# stromplatine3.net
KiCad netlist of a schematic drawn in EAGLE
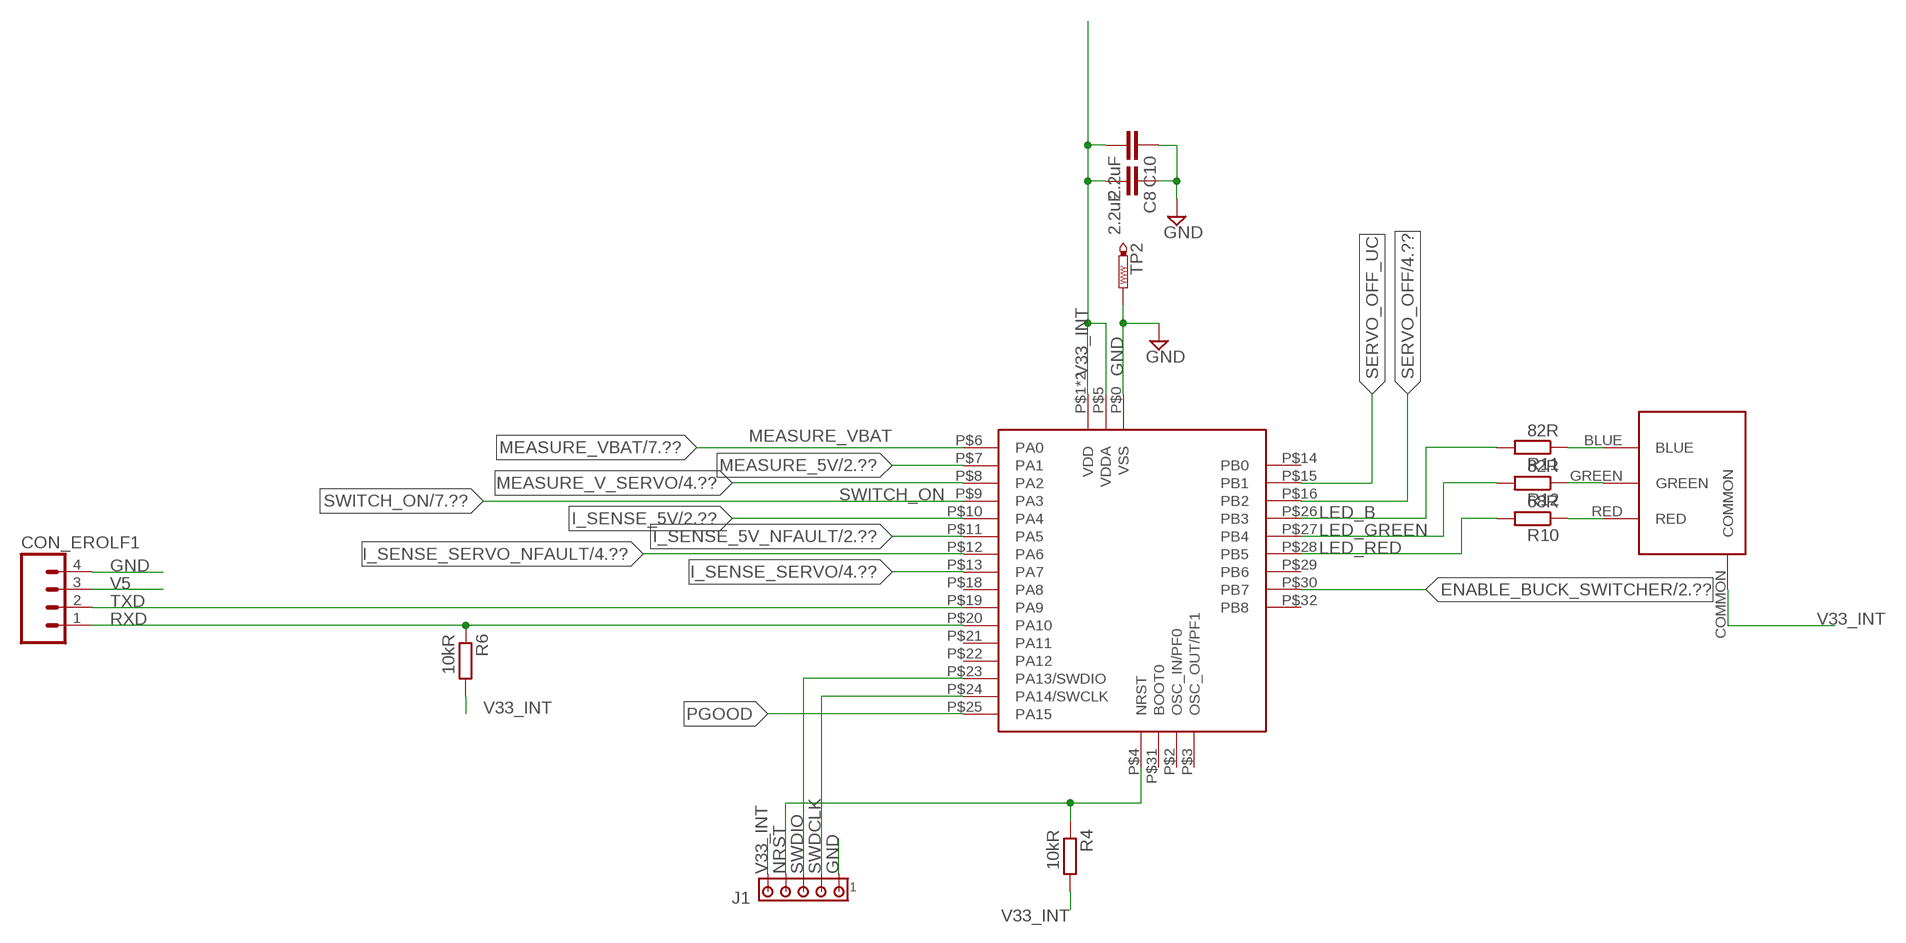
[diagram p0: schematic, sheet 1]
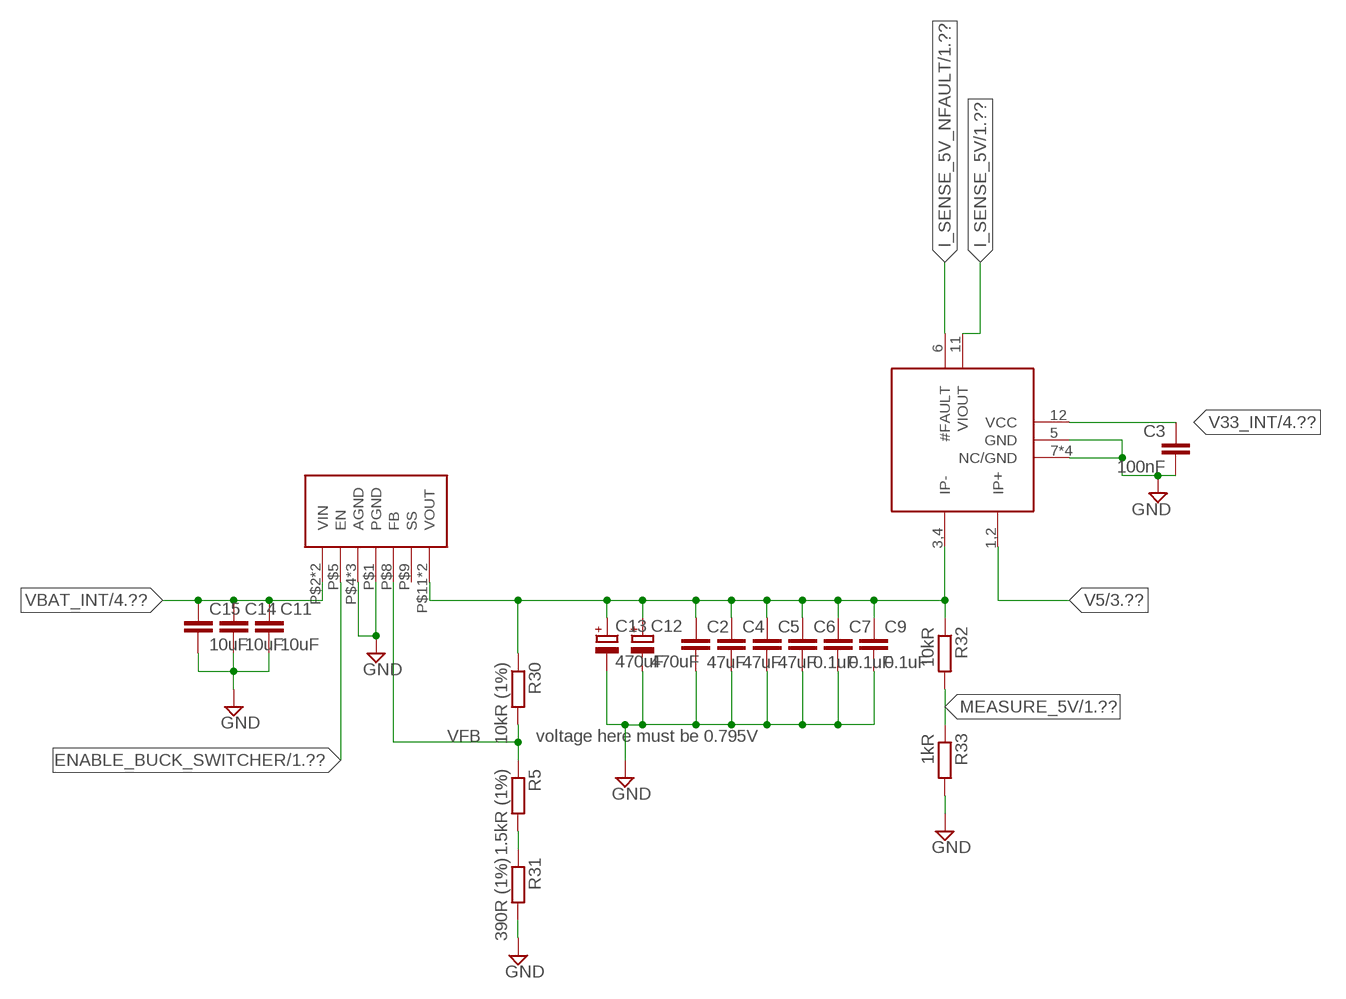
[diagram p1: schematic, sheet 2]
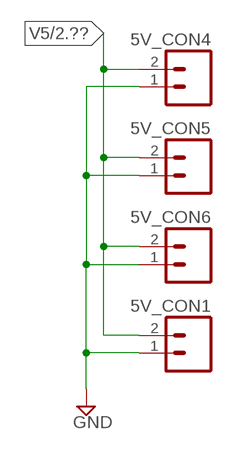
[diagram p2: schematic, sheet 3]
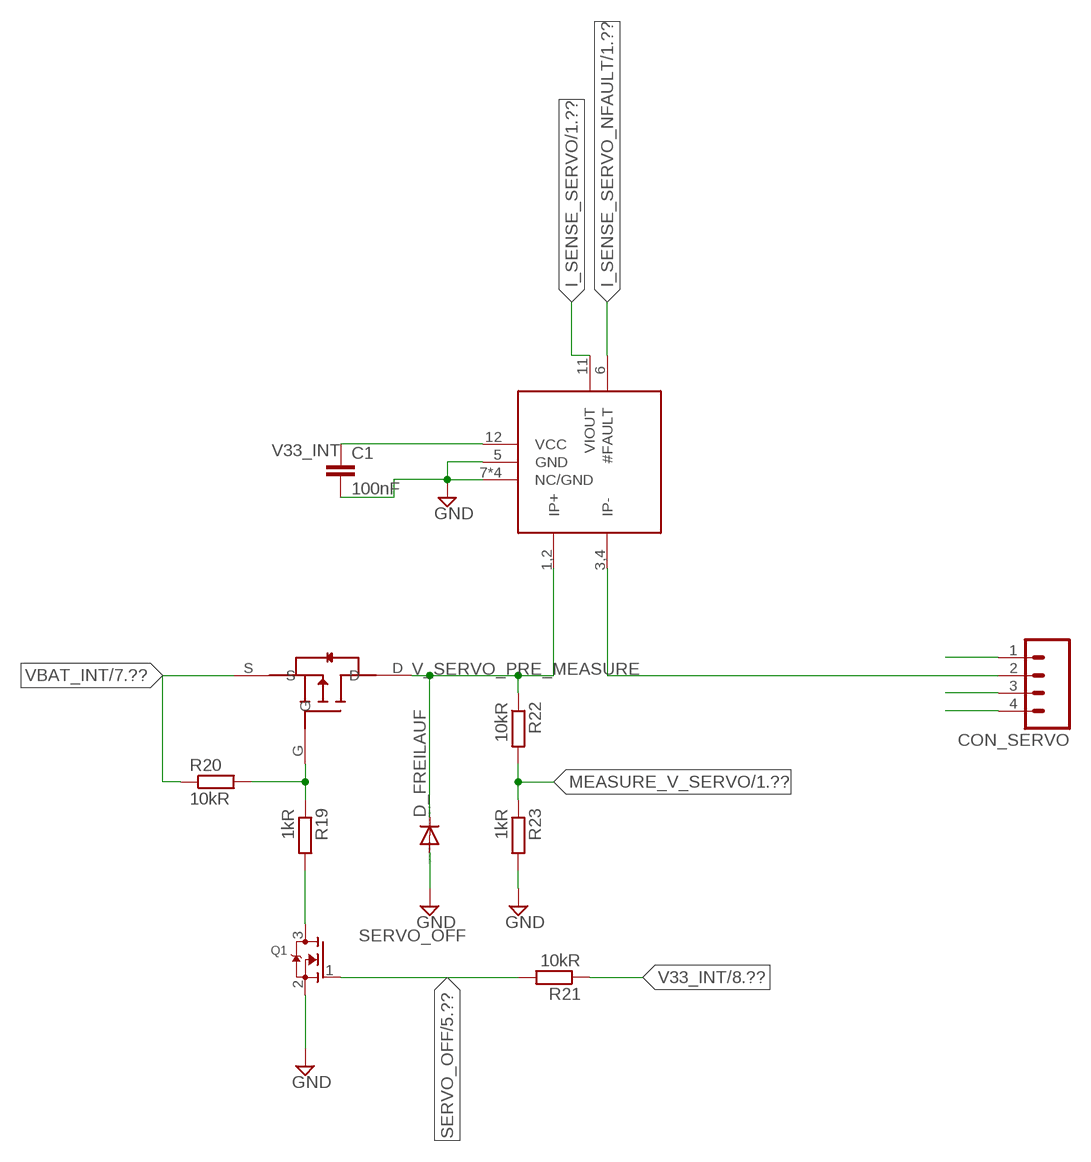
[diagram p3: schematic, sheet 4]
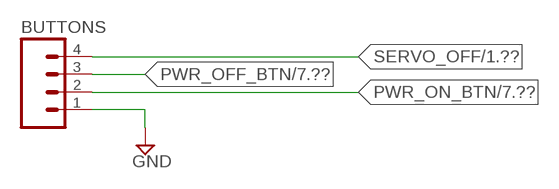
[diagram p4: schematic, sheet 5]
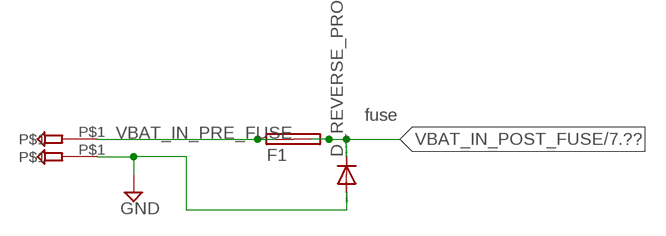
[diagram p5: schematic, sheet 6]
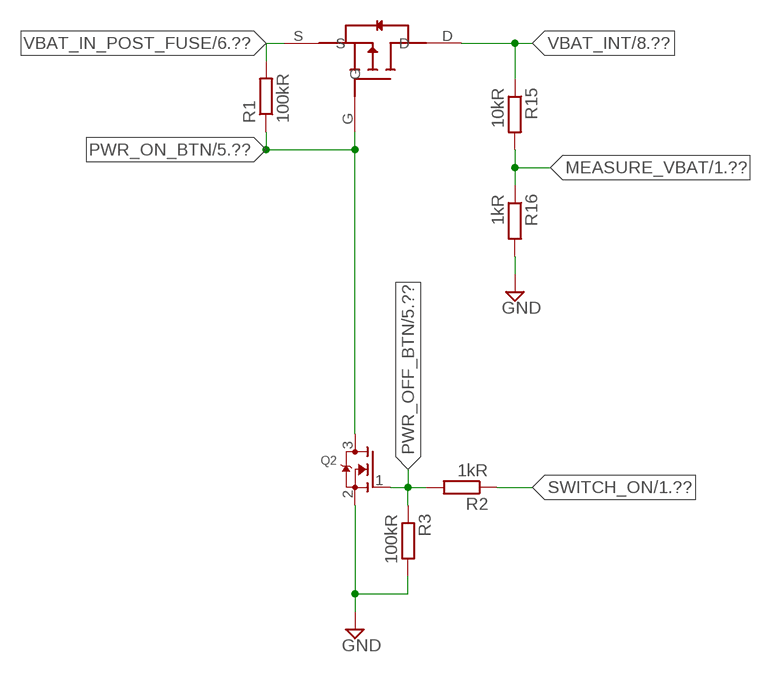
[diagram p6: schematic, sheet 7]
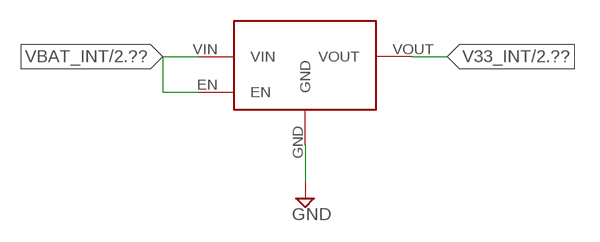
[diagram p7: schematic, sheet 8]
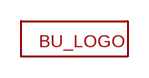
[diagram p8: schematic, sheet 9]

(export (version "E")
  (design (tool "Eeschema 10.0.6"))
  (components
    (comp (ref "U$5")
      (value "LOGO")
      (footprint "eagle-import:LOGO")
      (libsource (lib "eagle-import") (part "LOGO"))
    )
    (comp (ref "5V_CON1")
      (value "M02")
      (footprint "eagle-import:02P")
      (libsource (lib "eagle-import") (part "M02"))
    )
    (comp (ref "5V_CON4")
      (value "M02")
      (footprint "eagle-import:02P")
      (libsource (lib "eagle-import") (part "M02"))
    )
    (comp (ref "5V_CON5")
      (value "M02")
      (footprint "eagle-import:02P")
      (libsource (lib "eagle-import") (part "M02"))
    )
    (comp (ref "5V_CON6")
      (value "M02")
      (footprint "eagle-import:02P")
      (libsource (lib "eagle-import") (part "M02"))
    )
    (comp (ref "Q2")
      (value "MOSFET-NREFLOW")
      (footprint "eagle-import:SOT23")
      (libsource (lib "eagle-import") (part "MOSFET-NREFLOW"))
    )
    (comp (ref "R1")
      (value "100kR")
      (footprint "eagle-import:R0603")
      (libsource (lib "eagle-import") (part "R-EU_R0603"))
    )
    (comp (ref "R2")
      (value "1kR")
      (footprint "eagle-import:R0603")
      (libsource (lib "eagle-import") (part "R-EU_R0603"))
    )
    (comp (ref "R3")
      (value "100kR")
      (footprint "eagle-import:R0603")
      (libsource (lib "eagle-import") (part "R-EU_R0603"))
    )
    (comp (ref "R15")
      (value "10kR")
      (footprint "eagle-import:R0603")
      (libsource (lib "eagle-import") (part "R-EU_R0603"))
    )
    (comp (ref "R16")
      (value "1kR")
      (footprint "eagle-import:R0603")
      (libsource (lib "eagle-import") (part "R-EU_R0603"))
    )
    (comp (ref "U$4")
      (value "MOSFET/AOD417")
      (footprint "eagle-import:TO-252")
      (libsource (lib "eagle-import") (part "MOSFET/AOD417"))
    )
    (comp (ref "C8")
      (value "2.2uF")
      (footprint "eagle-import:C0402")
      (libsource (lib "eagle-import") (part "C-EUC0402"))
    )
    (comp (ref "C10")
      (value "2.2uF")
      (footprint "eagle-import:C0402")
      (libsource (lib "eagle-import") (part "C-EUC0402"))
    )
    (comp (ref "CON_EROLF1")
      (value "M04")
      (footprint "eagle-import:04P")
      (fields (field (name "OC_FARNELL") "unknown") (field (name "OC_NEWARK") "unknown"))
      (libsource (lib "eagle-import") (part "M04"))
    )
    (comp (ref "J1")
      (value "MTA05-100")
      (footprint "eagle-import:10X05MTA")
      (libsource (lib "eagle-import") (part "MTA05-100"))
    )
    (comp (ref "R4")
      (value "10kR")
      (footprint "eagle-import:R0603")
      (libsource (lib "eagle-import") (part "R-EU_R0603"))
    )
    (comp (ref "R6")
      (value "10kR")
      (footprint "eagle-import:R0603")
      (libsource (lib "eagle-import") (part "R-EU_R0603"))
    )
    (comp (ref "R10")
      (value "68R")
      (footprint "eagle-import:R0603")
      (libsource (lib "eagle-import") (part "R-EU_R0603"))
    )
    (comp (ref "R11")
      (value "82R")
      (footprint "eagle-import:R0603")
      (libsource (lib "eagle-import") (part "R-EU_R0603"))
    )
    (comp (ref "R12")
      (value "82R")
      (footprint "eagle-import:R0603")
      (libsource (lib "eagle-import") (part "R-EU_R0603"))
    )
    (comp (ref "TP2")
      (value "PTR1B1,27")
      (footprint "eagle-import:B1,27")
      (libsource (lib "eagle-import") (part "PTR1B1,27"))
    )
    (comp (ref "U$1")
      (value "STM32F051K8")
      (footprint "eagle-import:UFQFPN32")
      (libsource (lib "eagle-import") (part "STM32F051K8"))
    )
    (comp (ref "U$3")
      (value "RGB-LED")
      (footprint "eagle-import:4-PLCC")
      (libsource (lib "eagle-import") (part "RGB-LED"))
    )
    (comp (ref "D_REVERSE_PROT")
      (value "DIODE-DO-214AC")
      (footprint "eagle-import:DO-214AC")
      (libsource (lib "eagle-import") (part "DIODE-DO-214AC"))
    )
    (comp (ref "F1")
      (value "SHK20Q")
      (footprint "eagle-import:SHK20Q")
      (libsource (lib "eagle-import") (part "SHK20Q"))
    )
    (comp (ref "U$8") (value "TP") (footprint "eagle-import:TP") (libsource (lib "eagle-import") (part "TP")))
    (comp (ref "U$9") (value "TP") (footprint "eagle-import:TP") (libsource (lib "eagle-import") (part "TP")))
    (comp (ref "U$2")
      (value "LDO/AP2204")
      (footprint "eagle-import:SOT-23-5")
      (libsource (lib "eagle-import") (part "LDO/AP2204"))
    )
    (comp (ref "BUTTONS")
      (value "M04")
      (footprint "eagle-import:04P")
      (fields (field (name "OC_FARNELL") "unknown") (field (name "OC_NEWARK") "unknown"))
      (libsource (lib "eagle-import") (part "M04"))
    )
    (comp (ref "C1")
      (value "100nF")
      (footprint "eagle-import:C0402")
      (libsource (lib "eagle-import") (part "C-EUC0402"))
    )
    (comp (ref "CON_SERVO")
      (value "M04")
      (footprint "eagle-import:04P")
      (fields (field (name "OC_FARNELL") "unknown") (field (name "OC_NEWARK") "unknown"))
      (libsource (lib "eagle-import") (part "M04"))
    )
    (comp (ref "D_FREILAUF")
      (value "DIODE-DO-214AC")
      (footprint "eagle-import:DO-214AC")
      (libsource (lib "eagle-import") (part "DIODE-DO-214AC"))
    )
    (comp (ref "Q1")
      (value "MOSFET-NREFLOW")
      (footprint "eagle-import:SOT23")
      (libsource (lib "eagle-import") (part "MOSFET-NREFLOW"))
    )
    (comp (ref "R19")
      (value "1kR")
      (footprint "eagle-import:R0603")
      (libsource (lib "eagle-import") (part "R-EU_R0603"))
    )
    (comp (ref "R20")
      (value "10kR")
      (footprint "eagle-import:R0603")
      (libsource (lib "eagle-import") (part "R-EU_R0603"))
    )
    (comp (ref "R21")
      (value "10kR")
      (footprint "eagle-import:R0603")
      (libsource (lib "eagle-import") (part "R-EU_R0603"))
    )
    (comp (ref "R22")
      (value "10kR")
      (footprint "eagle-import:R0603")
      (libsource (lib "eagle-import") (part "R-EU_R0603"))
    )
    (comp (ref "R23")
      (value "1kR")
      (footprint "eagle-import:R0603")
      (libsource (lib "eagle-import") (part "R-EU_R0603"))
    )
    (comp (ref "U$6")
      (value "ACS711")
      (footprint "eagle-import:QFN-12-EX")
      (libsource (lib "eagle-import") (part "ACS711"))
    )
    (comp (ref "U$7")
      (value "MOSFET/AOD417")
      (footprint "eagle-import:TO-252")
      (libsource (lib "eagle-import") (part "MOSFET/AOD417"))
    )
    (comp (ref "C2")
      (value "47uF")
      (footprint "eagle-import:C1206")
      (libsource (lib "eagle-import") (part "C-EUC1206"))
    )
    (comp (ref "C3")
      (value "100nF")
      (footprint "eagle-import:C0402")
      (libsource (lib "eagle-import") (part "C-EUC0402"))
    )
    (comp (ref "C4")
      (value "47uF")
      (footprint "eagle-import:C1206")
      (libsource (lib "eagle-import") (part "C-EUC1206"))
    )
    (comp (ref "C5")
      (value "47uF")
      (footprint "eagle-import:C1206")
      (libsource (lib "eagle-import") (part "C-EUC1206"))
    )
    (comp (ref "C6")
      (value "0.1uF")
      (footprint "eagle-import:C0603")
      (libsource (lib "eagle-import") (part "C-EUC0603"))
    )
    (comp (ref "C7")
      (value "0.1uF")
      (footprint "eagle-import:C0603")
      (libsource (lib "eagle-import") (part "C-EUC0603"))
    )
    (comp (ref "C9")
      (value "0.1uF")
      (footprint "eagle-import:C0603")
      (libsource (lib "eagle-import") (part "C-EUC0603"))
    )
    (comp (ref "C11")
      (value "10uF")
      (footprint "eagle-import:C1206")
      (libsource (lib "eagle-import") (part "C-EUC1206"))
    )
    (comp (ref "C12")
      (value "470uF")
      (footprint "eagle-import:175TMP-0810")
      (libsource (lib "eagle-import") (part "CPOL-EU175TMP-0810"))
    )
    (comp (ref "C13")
      (value "470uF")
      (footprint "eagle-import:175TMP-0810")
      (libsource (lib "eagle-import") (part "CPOL-EU175TMP-0810"))
    )
    (comp (ref "C14")
      (value "10uF")
      (footprint "eagle-import:C1206")
      (libsource (lib "eagle-import") (part "C-EUC1206"))
    )
    (comp (ref "C15")
      (value "10uF")
      (footprint "eagle-import:C1206")
      (libsource (lib "eagle-import") (part "C-EUC1206"))
    )
    (comp (ref "R5")
      (value "1.5kR (1%)")
      (footprint "eagle-import:R0603")
      (libsource (lib "eagle-import") (part "R-EU_R0603"))
    )
    (comp (ref "R30")
      (value "10kR (1%)")
      (footprint "eagle-import:R0603")
      (libsource (lib "eagle-import") (part "R-EU_R0603"))
    )
    (comp (ref "R31")
      (value "390R (1%)")
      (footprint "eagle-import:R0603")
      (libsource (lib "eagle-import") (part "R-EU_R0603"))
    )
    (comp (ref "R32")
      (value "10kR")
      (footprint "eagle-import:R0603")
      (libsource (lib "eagle-import") (part "R-EU_R0603"))
    )
    (comp (ref "R33")
      (value "1kR")
      (footprint "eagle-import:R0603")
      (libsource (lib "eagle-import") (part "R-EU_R0603"))
    )
    (comp (ref "U$10")
      (value "ACS711")
      (footprint "eagle-import:QFN-12-EX")
      (libsource (lib "eagle-import") (part "ACS711"))
    )
    (comp (ref "U$11")
      (value "LMZ12010")
      (footprint "eagle-import:TZA11A")
      (libsource (lib "eagle-import") (part "LMZ12010"))
    )
  )
  (nets
    (net (code "1") (name "ENABLE_BUCK_SWITCHER") (class "Default")
      (node (ref "U$1") (pin "P$30") (pinfunction "PB7_P$30") (pintype "bidirectional"))
      (node (ref "U$11") (pin "P$5") (pinfunction "EN_P$5") (pintype "bidirectional"))
    )
    (net (code "2") (name "GND") (class "Default")
      (node (ref "5V_CON1") (pin "1") (pinfunction "1_1") (pintype "passive"))
      (node (ref "5V_CON4") (pin "1") (pinfunction "1_1") (pintype "passive"))
      (node (ref "5V_CON5") (pin "1") (pinfunction "1_1") (pintype "passive"))
      (node (ref "5V_CON6") (pin "1") (pinfunction "1_1") (pintype "passive"))
      (node (ref "BUTTONS") (pin "1") (pinfunction "1_1") (pintype "passive"))
      (node (ref "C1") (pin "2") (pinfunction "2_2") (pintype "passive"))
      (node (ref "C10") (pin "1") (pinfunction "1_1") (pintype "passive"))
      (node (ref "C11") (pin "2") (pinfunction "2_2") (pintype "passive"))
      (node (ref "C12") (pin "-") (pinfunction "-_-") (pintype "passive"))
      (node (ref "C13") (pin "-") (pinfunction "-_-") (pintype "passive"))
      (node (ref "C14") (pin "2") (pinfunction "2_2") (pintype "passive"))
      (node (ref "C15") (pin "2") (pinfunction "2_2") (pintype "passive"))
      (node (ref "C2") (pin "2") (pinfunction "2_2") (pintype "passive"))
      (node (ref "C3") (pin "2") (pinfunction "2_2") (pintype "passive"))
      (node (ref "C4") (pin "2") (pinfunction "2_2") (pintype "passive"))
      (node (ref "C5") (pin "2") (pinfunction "2_2") (pintype "passive"))
      (node (ref "C6") (pin "2") (pinfunction "2_2") (pintype "passive"))
      (node (ref "C7") (pin "2") (pinfunction "2_2") (pintype "passive"))
      (node (ref "C8") (pin "1") (pinfunction "1_1") (pintype "passive"))
      (node (ref "C9") (pin "2") (pinfunction "2_2") (pintype "passive"))
      (node (ref "CON_EROLF1") (pin "4") (pinfunction "4_4") (pintype "passive"))
      (node (ref "CON_SERVO") (pin "1") (pinfunction "1_1") (pintype "passive"))
      (node (ref "D_FREILAUF") (pin "A") (pinfunction "A_A") (pintype "passive"))
      (node (ref "D_REVERSE_PROT") (pin "A") (pinfunction "A_A") (pintype "passive"))
      (node (ref "J1") (pin "1") (pinfunction "1_1") (pintype "passive"))
      (node (ref "Q1") (pin "2") (pinfunction "S_2") (pintype "bidirectional"))
      (node (ref "Q2") (pin "2") (pinfunction "S_2") (pintype "bidirectional"))
      (node (ref "R16") (pin "2") (pinfunction "2_2") (pintype "passive"))
      (node (ref "R23") (pin "2") (pinfunction "2_2") (pintype "passive"))
      (node (ref "R3") (pin "2") (pinfunction "2_2") (pintype "passive"))
      (node (ref "R31") (pin "2") (pinfunction "2_2") (pintype "passive"))
      (node (ref "R33") (pin "2") (pinfunction "2_2") (pintype "passive"))
      (node (ref "TP2") (pin "TP") (pinfunction "TP_TP") (pintype "input"))
      (node (ref "U$1") (pin "P$0") (pinfunction "VSS_P$0") (pintype "bidirectional"))
      (node (ref "U$10") (pin "10") (pinfunction "NC/GND_10") (pintype "bidirectional"))
      (node (ref "U$10") (pin "5") (pinfunction "GND_5") (pintype "bidirectional"))
      (node (ref "U$10") (pin "7") (pinfunction "NC/GND_7") (pintype "bidirectional"))
      (node (ref "U$10") (pin "8") (pinfunction "NC/GND_8") (pintype "bidirectional"))
      (node (ref "U$10") (pin "9") (pinfunction "NC/GND_9") (pintype "bidirectional"))
      (node (ref "U$11") (pin "P$1") (pinfunction "PGND_P$1") (pintype "bidirectional"))
      (node (ref "U$11") (pin "P$4") (pinfunction "AGND_P$4") (pintype "bidirectional"))
      (node (ref "U$11") (pin "P$6") (pinfunction "AGND_P$6") (pintype "bidirectional"))
      (node (ref "U$11") (pin "P$7") (pinfunction "AGND_P$7") (pintype "bidirectional"))
      (node (ref "U$2") (pin "GND") (pinfunction "GND_GND") (pintype "bidirectional"))
      (node (ref "U$6") (pin "10") (pinfunction "NC/GND_10") (pintype "bidirectional"))
      (node (ref "U$6") (pin "5") (pinfunction "GND_5") (pintype "bidirectional"))
      (node (ref "U$6") (pin "7") (pinfunction "NC/GND_7") (pintype "bidirectional"))
      (node (ref "U$6") (pin "8") (pinfunction "NC/GND_8") (pintype "bidirectional"))
      (node (ref "U$6") (pin "9") (pinfunction "NC/GND_9") (pintype "bidirectional"))
      (node (ref "U$9") (pin "P$1") (pinfunction "P$1_P$1") (pintype "bidirectional"))
    )
    (net (code "3") (name "I_SENSE_5V") (class "Default")
      (node (ref "U$1") (pin "P$10") (pinfunction "PA4_P$10") (pintype "bidirectional"))
      (node (ref "U$10") (pin "11") (pinfunction "VIOUT_11") (pintype "bidirectional"))
    )
    (net (code "4") (name "I_SENSE_5V_NFAULT") (class "Default")
      (node (ref "U$1") (pin "P$11") (pinfunction "PA5_P$11") (pintype "bidirectional"))
      (node (ref "U$10") (pin "6") (pinfunction "#FAULT_6") (pintype "bidirectional"))
    )
    (net (code "5") (name "I_SENSE_SERVO") (class "Default")
      (node (ref "U$1") (pin "P$13") (pinfunction "PA7_P$13") (pintype "bidirectional"))
      (node (ref "U$6") (pin "11") (pinfunction "VIOUT_11") (pintype "bidirectional"))
    )
    (net (code "6") (name "I_SENSE_SERVO_NFAULT") (class "Default")
      (node (ref "U$1") (pin "P$12") (pinfunction "PA6_P$12") (pintype "bidirectional"))
      (node (ref "U$6") (pin "6") (pinfunction "#FAULT_6") (pintype "bidirectional"))
    )
    (net (code "7") (name "LED_B") (class "Default")
      (node (ref "R11") (pin "2") (pinfunction "2_2") (pintype "passive"))
      (node (ref "U$1") (pin "P$26") (pinfunction "PB3_P$26") (pintype "bidirectional"))
    )
    (net (code "8") (name "LED_GREEN") (class "Default")
      (node (ref "R12") (pin "2") (pinfunction "2_2") (pintype "passive"))
      (node (ref "U$1") (pin "P$27") (pinfunction "PB4_P$27") (pintype "bidirectional"))
    )
    (net (code "9") (name "LED_RED") (class "Default")
      (node (ref "R10") (pin "2") (pinfunction "2_2") (pintype "passive"))
      (node (ref "U$1") (pin "P$28") (pinfunction "PB5_P$28") (pintype "bidirectional"))
    )
    (net (code "10") (name "MEASURE_5V") (class "Default")
      (node (ref "R32") (pin "2") (pinfunction "2_2") (pintype "passive"))
      (node (ref "R33") (pin "1") (pinfunction "1_1") (pintype "passive"))
      (node (ref "U$1") (pin "P$7") (pinfunction "PA1_P$7") (pintype "bidirectional"))
    )
    (net (code "11") (name "MEASURE_VBAT") (class "Default")
      (node (ref "R15") (pin "2") (pinfunction "2_2") (pintype "passive"))
      (node (ref "R16") (pin "1") (pinfunction "1_1") (pintype "passive"))
      (node (ref "U$1") (pin "P$6") (pinfunction "PA0_P$6") (pintype "bidirectional"))
    )
    (net (code "12") (name "MEASURE_V_SERVO") (class "Default")
      (node (ref "R22") (pin "2") (pinfunction "2_2") (pintype "passive"))
      (node (ref "R23") (pin "1") (pinfunction "1_1") (pintype "passive"))
      (node (ref "U$1") (pin "P$8") (pinfunction "PA2_P$8") (pintype "bidirectional"))
    )
    (net (code "13") (name "NRST") (class "Default")
      (node (ref "J1") (pin "4") (pinfunction "4_4") (pintype "passive"))
      (node (ref "R4") (pin "1") (pinfunction "1_1") (pintype "passive"))
      (node (ref "U$1") (pin "P$4") (pinfunction "NRST_P$4") (pintype "bidirectional"))
    )
    (net (code "14") (name "Net-(Q1-D)") (class "Default")
      (node (ref "Q1") (pin "3") (pinfunction "D_3") (pintype "bidirectional"))
      (node (ref "R19") (pin "2") (pinfunction "2_2") (pintype "passive"))
    )
    (net (code "15") (name "Net-(R10-Pad1)") (class "Default")
      (node (ref "R10") (pin "1") (pinfunction "1_1") (pintype "passive"))
      (node (ref "U$3") (pin "RED") (pinfunction "RED_RED") (pintype "bidirectional"))
    )
    (net (code "16") (name "Net-(R11-Pad1)") (class "Default")
      (node (ref "R11") (pin "1") (pinfunction "1_1") (pintype "passive"))
      (node (ref "U$3") (pin "BLUE") (pinfunction "BLUE_BLUE") (pintype "bidirectional"))
    )
    (net (code "17") (name "Net-(R12-Pad1)") (class "Default")
      (node (ref "R12") (pin "1") (pinfunction "1_1") (pintype "passive"))
      (node (ref "U$3") (pin "GREEN") (pinfunction "GREEN_GREEN") (pintype "bidirectional"))
    )
    (net (code "18") (name "Net-(R19-Pad1)") (class "Default")
      (node (ref "R19") (pin "1") (pinfunction "1_1") (pintype "passive"))
      (node (ref "R20") (pin "2") (pinfunction "2_2") (pintype "passive"))
      (node (ref "U$7") (pin "G") (pinfunction "G_G") (pintype "bidirectional"))
    )
    (net (code "19") (name "Net-(R31-Pad1)") (class "Default")
      (node (ref "R31") (pin "1") (pinfunction "1_1") (pintype "passive"))
      (node (ref "R5") (pin "2") (pinfunction "2_2") (pintype "passive"))
    )
    (net (code "20") (name "Net-(U$6-IP-)") (class "Default")
      (node (ref "CON_SERVO") (pin "2") (pinfunction "2_2") (pintype "passive"))
      (node (ref "U$6") (pin "3,4") (pinfunction "IP-_3,4") (pintype "bidirectional"))
    )
    (net (code "21") (name "Net-(U$10-IP-)") (class "Default")
      (node (ref "C12") (pin "+") (pinfunction "+_+") (pintype "passive"))
      (node (ref "C13") (pin "+") (pinfunction "+_+") (pintype "passive"))
      (node (ref "C2") (pin "1") (pinfunction "1_1") (pintype "passive"))
      (node (ref "C4") (pin "1") (pinfunction "1_1") (pintype "passive"))
      (node (ref "C5") (pin "1") (pinfunction "1_1") (pintype "passive"))
      (node (ref "C6") (pin "1") (pinfunction "1_1") (pintype "passive"))
      (node (ref "C7") (pin "1") (pinfunction "1_1") (pintype "passive"))
      (node (ref "C9") (pin "1") (pinfunction "1_1") (pintype "passive"))
      (node (ref "R30") (pin "1") (pinfunction "1_1") (pintype "passive"))
      (node (ref "R32") (pin "1") (pinfunction "1_1") (pintype "passive"))
      (node (ref "U$10") (pin "3,4") (pinfunction "IP-_3,4") (pintype "bidirectional"))
      (node (ref "U$11") (pin "P$11") (pinfunction "VOUT_P$11") (pintype "bidirectional"))
      (node (ref "U$11") (pin "P$12") (pinfunction "VOUT_P$12") (pintype "bidirectional"))
    )
    (net (code "22") (name "PGOOD") (class "Default")
      (node (ref "U$1") (pin "P$25") (pinfunction "PA15_P$25") (pintype "bidirectional"))
    )
    (net (code "23") (name "PWR_OFF_BTN") (class "Default")
      (node (ref "BUTTONS") (pin "3") (pinfunction "3_3") (pintype "passive"))
      (node (ref "Q2") (pin "1") (pinfunction "G_1") (pintype "bidirectional"))
      (node (ref "R2") (pin "2") (pinfunction "2_2") (pintype "passive"))
      (node (ref "R3") (pin "1") (pinfunction "1_1") (pintype "passive"))
    )
    (net (code "24") (name "PWR_ON_BTN") (class "Default")
      (node (ref "BUTTONS") (pin "2") (pinfunction "2_2") (pintype "passive"))
      (node (ref "Q2") (pin "3") (pinfunction "D_3") (pintype "bidirectional"))
      (node (ref "R1") (pin "1") (pinfunction "1_1") (pintype "passive"))
      (node (ref "U$4") (pin "G") (pinfunction "G_G") (pintype "bidirectional"))
    )
    (net (code "25") (name "RXD") (class "Default")
      (node (ref "CON_EROLF1") (pin "1") (pinfunction "1_1") (pintype "passive"))
      (node (ref "R6") (pin "1") (pinfunction "1_1") (pintype "passive"))
      (node (ref "U$1") (pin "P$20") (pinfunction "PA10_P$20") (pintype "bidirectional"))
    )
    (net (code "26") (name "SERVO_OFF") (class "Default")
      (node (ref "BUTTONS") (pin "4") (pinfunction "4_4") (pintype "passive"))
      (node (ref "Q1") (pin "1") (pinfunction "G_1") (pintype "bidirectional"))
      (node (ref "R21") (pin "2") (pinfunction "2_2") (pintype "passive"))
      (node (ref "U$1") (pin "P$16") (pinfunction "PB2_P$16") (pintype "bidirectional"))
    )
    (net (code "27") (name "SERVO_OFF_UC") (class "Default")
      (node (ref "U$1") (pin "P$15") (pinfunction "PB1_P$15") (pintype "bidirectional"))
    )
    (net (code "28") (name "SWDCLK") (class "Default")
      (node (ref "J1") (pin "2") (pinfunction "2_2") (pintype "passive"))
      (node (ref "U$1") (pin "P$24") (pinfunction "PA14/SWCLK_P$24") (pintype "bidirectional"))
    )
    (net (code "29") (name "SWDIO") (class "Default")
      (node (ref "J1") (pin "3") (pinfunction "3_3") (pintype "passive"))
      (node (ref "U$1") (pin "P$23") (pinfunction "PA13/SWDIO_P$23") (pintype "bidirectional"))
    )
    (net (code "30") (name "SWITCH_ON") (class "Default")
      (node (ref "R2") (pin "1") (pinfunction "1_1") (pintype "passive"))
      (node (ref "U$1") (pin "P$9") (pinfunction "PA3_P$9") (pintype "bidirectional"))
    )
    (net (code "31") (name "TXD") (class "Default")
      (node (ref "CON_EROLF1") (pin "2") (pinfunction "2_2") (pintype "passive"))
      (node (ref "U$1") (pin "P$19") (pinfunction "PA9_P$19") (pintype "bidirectional"))
    )
    (net (code "32") (name "V5") (class "Default")
      (node (ref "5V_CON1") (pin "2") (pinfunction "2_2") (pintype "passive"))
      (node (ref "5V_CON4") (pin "2") (pinfunction "2_2") (pintype "passive"))
      (node (ref "5V_CON5") (pin "2") (pinfunction "2_2") (pintype "passive"))
      (node (ref "5V_CON6") (pin "2") (pinfunction "2_2") (pintype "passive"))
      (node (ref "CON_EROLF1") (pin "3") (pinfunction "3_3") (pintype "passive"))
      (node (ref "U$10") (pin "1,2") (pinfunction "IP+_1,2") (pintype "bidirectional"))
    )
    (net (code "33") (name "V33_INT") (class "Default")
      (node (ref "C1") (pin "1") (pinfunction "1_1") (pintype "passive"))
      (node (ref "C10") (pin "2") (pinfunction "2_2") (pintype "passive"))
      (node (ref "C3") (pin "1") (pinfunction "1_1") (pintype "passive"))
      (node (ref "C8") (pin "2") (pinfunction "2_2") (pintype "passive"))
      (node (ref "J1") (pin "5") (pinfunction "5_5") (pintype "passive"))
      (node (ref "R21") (pin "1") (pinfunction "1_1") (pintype "passive"))
      (node (ref "R4") (pin "2") (pinfunction "2_2") (pintype "passive"))
      (node (ref "R6") (pin "2") (pinfunction "2_2") (pintype "passive"))
      (node (ref "U$1") (pin "P$1") (pinfunction "VDD_P$1") (pintype "bidirectional"))
      (node (ref "U$1") (pin "P$17") (pinfunction "VDD_P$17") (pintype "bidirectional"))
      (node (ref "U$1") (pin "P$5") (pinfunction "VDDA_P$5") (pintype "bidirectional"))
      (node (ref "U$10") (pin "12") (pinfunction "VCC_12") (pintype "bidirectional"))
      (node (ref "U$2") (pin "VOUT") (pinfunction "VOUT_VOUT") (pintype "bidirectional"))
      (node (ref "U$3") (pin "COMMON") (pinfunction "COMMON_COMMON") (pintype "bidirectional"))
      (node (ref "U$6") (pin "12") (pinfunction "VCC_12") (pintype "bidirectional"))
    )
    (net (code "34") (name "VBAT_INT") (class "Default")
      (node (ref "C11") (pin "1") (pinfunction "1_1") (pintype "passive"))
      (node (ref "C14") (pin "1") (pinfunction "1_1") (pintype "passive"))
      (node (ref "C15") (pin "1") (pinfunction "1_1") (pintype "passive"))
      (node (ref "R15") (pin "1") (pinfunction "1_1") (pintype "passive"))
      (node (ref "R20") (pin "1") (pinfunction "1_1") (pintype "passive"))
      (node (ref "U$11") (pin "P$2") (pinfunction "VIN_P$2") (pintype "bidirectional"))
      (node (ref "U$11") (pin "P$3") (pinfunction "VIN_P$3") (pintype "bidirectional"))
      (node (ref "U$2") (pin "EN") (pinfunction "EN_EN") (pintype "bidirectional"))
      (node (ref "U$2") (pin "VIN") (pinfunction "VIN_VIN") (pintype "bidirectional"))
      (node (ref "U$4") (pin "D") (pinfunction "D_D") (pintype "bidirectional"))
      (node (ref "U$7") (pin "S") (pinfunction "S_S") (pintype "bidirectional"))
    )
    (net (code "35") (name "VBAT_IN_POST_FUSE") (class "Default")
      (node (ref "D_REVERSE_PROT") (pin "C") (pinfunction "C_C") (pintype "passive"))
      (node (ref "F1") (pin "2A") (pinfunction "2A_2A") (pintype "passive"))
      (node (ref "F1") (pin "2B") (pinfunction "2B_2B") (pintype "passive"))
      (node (ref "R1") (pin "2") (pinfunction "2_2") (pintype "passive"))
      (node (ref "U$4") (pin "S") (pinfunction "S_S") (pintype "bidirectional"))
    )
    (net (code "36") (name "VBAT_IN_PRE_FUSE") (class "Default")
      (node (ref "F1") (pin "1A") (pinfunction "1A_1A") (pintype "passive"))
      (node (ref "F1") (pin "1B") (pinfunction "1B_1B") (pintype "passive"))
      (node (ref "U$8") (pin "P$1") (pinfunction "P$1_P$1") (pintype "bidirectional"))
    )
    (net (code "37") (name "VFB") (class "Default")
      (node (ref "R30") (pin "2") (pinfunction "2_2") (pintype "passive"))
      (node (ref "R5") (pin "1") (pinfunction "1_1") (pintype "passive"))
      (node (ref "U$11") (pin "P$8") (pinfunction "FB_P$8") (pintype "bidirectional"))
    )
    (net (code "38") (name "V_SERVO_PRE_MEASURE") (class "Default")
      (node (ref "D_FREILAUF") (pin "C") (pinfunction "C_C") (pintype "passive"))
      (node (ref "R22") (pin "1") (pinfunction "1_1") (pintype "passive"))
      (node (ref "U$6") (pin "1,2") (pinfunction "IP+_1,2") (pintype "bidirectional"))
      (node (ref "U$7") (pin "D") (pinfunction "D_D") (pintype "bidirectional"))
    )
    (net (code "39") (name "unconnected-(CON_SERVO-Pad3)") (class "Default")
      (node (ref "CON_SERVO") (pin "3") (pinfunction "3_3") (pintype "passive"))
    )
    (net (code "40") (name "unconnected-(CON_SERVO-Pad4)") (class "Default")
      (node (ref "CON_SERVO") (pin "4") (pinfunction "4_4") (pintype "passive"))
    )
    (net (code "41") (name "unconnected-(U$1-BOOT0-PadP$31)") (class "Default")
      (node (ref "U$1") (pin "P$31") (pinfunction "BOOT0_P$31") (pintype "bidirectional"))
    )
    (net (code "42") (name "unconnected-(U$1-OSC_IN{slash}PF0-PadP$2)") (class "Default")
      (node (ref "U$1") (pin "P$2") (pinfunction "OSC_IN/PF0_P$2") (pintype "bidirectional"))
    )
    (net (code "43") (name "unconnected-(U$1-OSC_OUT{slash}PF1-PadP$3)") (class "Default")
      (node (ref "U$1") (pin "P$3") (pinfunction "OSC_OUT/PF1_P$3") (pintype "bidirectional"))
    )
    (net (code "44") (name "unconnected-(U$1-PA8-PadP$18)") (class "Default")
      (node (ref "U$1") (pin "P$18") (pinfunction "PA8_P$18") (pintype "bidirectional"))
    )
    (net (code "45") (name "unconnected-(U$1-PA11-PadP$21)") (class "Default")
      (node (ref "U$1") (pin "P$21") (pinfunction "PA11_P$21") (pintype "bidirectional"))
    )
    (net (code "46") (name "unconnected-(U$1-PA12-PadP$22)") (class "Default")
      (node (ref "U$1") (pin "P$22") (pinfunction "PA12_P$22") (pintype "bidirectional"))
    )
    (net (code "47") (name "unconnected-(U$1-PB0-PadP$14)") (class "Default")
      (node (ref "U$1") (pin "P$14") (pinfunction "PB0_P$14") (pintype "bidirectional"))
    )
    (net (code "48") (name "unconnected-(U$1-PB6-PadP$29)") (class "Default")
      (node (ref "U$1") (pin "P$29") (pinfunction "PB6_P$29") (pintype "bidirectional"))
    )
    (net (code "49") (name "unconnected-(U$1-PB8-PadP$32)") (class "Default")
      (node (ref "U$1") (pin "P$32") (pinfunction "PB8_P$32") (pintype "bidirectional"))
    )
    (net (code "50") (name "unconnected-(U$11-SS-PadP$9)") (class "Default")
      (node (ref "U$11") (pin "P$9") (pinfunction "SS_P$9") (pintype "bidirectional"))
    )
  )
)
